# tempctl.net
KiCad netlist of a schematic drawn in EAGLE
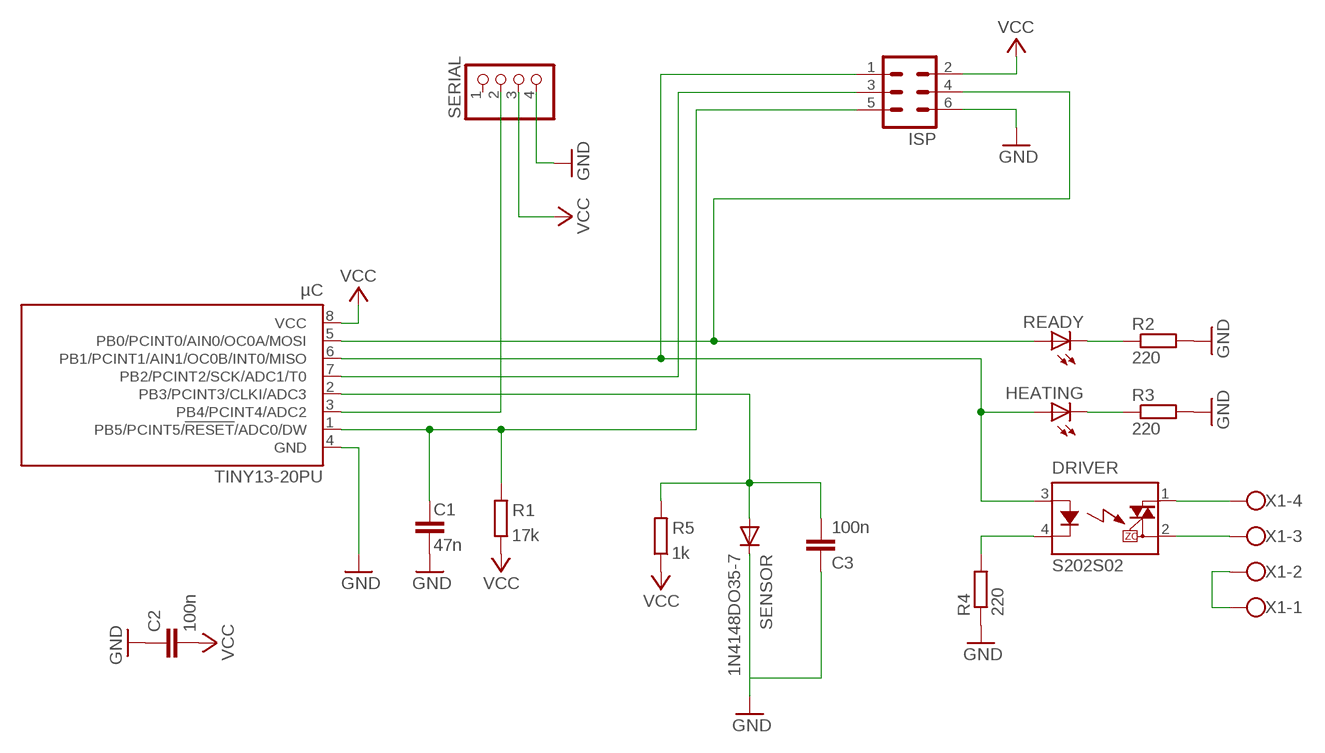
[diagram p0: schematic, sheet 1]

(export (version "E")
  (design (tool "Eeschema 10.0.6"))
  (components
    (comp (ref "C1")
      (value "47n")
      (footprint "eagle-import:C075-032X103")
      (libsource (lib "eagle-import") (part "C-EU075-032X103"))
    )
    (comp (ref "C2")
      (value "100n")
      (footprint "eagle-import:C102-043X133")
      (libsource (lib "eagle-import") (part "C-EU102-043X133"))
    )
    (comp (ref "C3")
      (value "100n")
      (footprint "eagle-import:C102-043X133")
      (libsource (lib "eagle-import") (part "C-EU102-043X133"))
    )
    (comp (ref "DRIVER")
      (value "S202S02")
      (footprint "eagle-import:S202S02")
      (fields (field (name "MPN") "S202S02F"))
      (libsource (lib "eagle-import") (part "S02S022"))
    )
    (comp (ref "HEATING")
      (value "LED3MM")
      (footprint "eagle-import:LED3MM")
      (libsource (lib "eagle-import") (part "LED3MM"))
    )
    (comp (ref "ISP")
      (value "ML6")
      (footprint "eagle-import:ML6")
      (libsource (lib "eagle-import") (part "ML6"))
    )
    (comp (ref "R1")
      (value "17k")
      (footprint "eagle-import:0207_10")
      (libsource (lib "eagle-import") (part "R-EU_0207/10"))
    )
    (comp (ref "R2")
      (value "220")
      (footprint "eagle-import:0309_12")
      (libsource (lib "eagle-import") (part "R-EU_0309/12"))
    )
    (comp (ref "R3")
      (value "220")
      (footprint "eagle-import:0309_12")
      (libsource (lib "eagle-import") (part "R-EU_0309/12"))
    )
    (comp (ref "R4")
      (value "220")
      (footprint "eagle-import:0309_12")
      (libsource (lib "eagle-import") (part "R-EU_0309/12"))
    )
    (comp (ref "R5")
      (value "1k")
      (footprint "eagle-import:0207_10")
      (libsource (lib "eagle-import") (part "R-EU_0207/10"))
    )
    (comp (ref "READY")
      (value "LED3MM")
      (footprint "eagle-import:LED3MM")
      (libsource (lib "eagle-import") (part "LED3MM"))
    )
    (comp (ref "SENSOR")
      (value "1N4148DO35-7")
      (footprint "eagle-import:DO35-7")
      (libsource (lib "eagle-import") (part "1N4148DO35-7"))
    )
    (comp (ref "SERIAL")
      (value "PINHD-1X4")
      (footprint "eagle-import:1X04")
      (libsource (lib "eagle-import") (part "PINHD-1X4"))
    )
    (comp (ref "X1")
      (value "W237-4")
      (footprint "eagle-import:W237-4")
      (libsource (lib "eagle-import") (part "W237-4"))
    )
    (comp (ref "µC")
      (value "TINY13-20PU")
      (footprint "eagle-import:DIL08")
      (fields (field (name "MPN") "ATTINY13-20PU"))
      (libsource (lib "eagle-import") (part "TINY13PU-20"))
    )
  )
  (nets
    (net (code "1") (name "GND") (class "Default")
      (node (ref "C1") (pin "2") (pinfunction "2_2") (pintype "passive"))
      (node (ref "C2") (pin "1") (pinfunction "1_1") (pintype "passive"))
      (node (ref "C3") (pin "1") (pinfunction "1_1") (pintype "passive"))
      (node (ref "ISP") (pin "6") (pinfunction "6_6") (pintype "passive"))
      (node (ref "R2") (pin "2") (pinfunction "2_2") (pintype "passive"))
      (node (ref "R3") (pin "2") (pinfunction "2_2") (pintype "passive"))
      (node (ref "R4") (pin "1") (pinfunction "1_1") (pintype "passive"))
      (node (ref "SENSOR") (pin "C") (pinfunction "C_C") (pintype "passive"))
      (node (ref "SERIAL") (pin "4") (pinfunction "4_4") (pintype "passive"))
      (node (ref "µC") (pin "4") (pinfunction "GND_4") (pintype "power_in"))
    )
    (net (code "2") (name "Net-(DRIVER-A)") (class "Default")
      (node (ref "DRIVER") (pin "3") (pinfunction "A_3") (pintype "passive"))
      (node (ref "HEATING") (pin "A") (pinfunction "A_A") (pintype "passive"))
      (node (ref "ISP") (pin "1") (pinfunction "1_1") (pintype "passive"))
      (node (ref "µC") (pin "6") (pinfunction "PB1/PCINT1/AIN1/OC0B/INT0/MISO_6") (pintype "bidirectional"))
    )
    (net (code "3") (name "Net-(DRIVER-DS1)") (class "Default")
      (node (ref "DRIVER") (pin "1") (pinfunction "DS1_1") (pintype "passive"))
      (node (ref "X1") (pin "4") (pinfunction "KL_4") (pintype "passive"))
    )
    (net (code "4") (name "Net-(DRIVER-DS2)") (class "Default")
      (node (ref "DRIVER") (pin "2") (pinfunction "DS2_2") (pintype "passive"))
      (node (ref "X1") (pin "3") (pinfunction "KL_3") (pintype "passive"))
    )
    (net (code "5") (name "Net-(DRIVER-K)") (class "Default")
      (node (ref "DRIVER") (pin "4") (pinfunction "K_4") (pintype "passive"))
      (node (ref "R4") (pin "2") (pinfunction "2_2") (pintype "passive"))
    )
    (net (code "6") (name "Net-(HEATING-C)") (class "Default")
      (node (ref "HEATING") (pin "K") (pinfunction "C_K") (pintype "passive"))
      (node (ref "R3") (pin "1") (pinfunction "1_1") (pintype "passive"))
    )
    (net (code "7") (name "Net-(READY-C)") (class "Default")
      (node (ref "R2") (pin "1") (pinfunction "1_1") (pintype "passive"))
      (node (ref "READY") (pin "K") (pinfunction "C_K") (pintype "passive"))
    )
    (net (code "8") (name "Net-(X1A-KL)") (class "Default")
      (node (ref "X1") (pin "1") (pinfunction "KL_1") (pintype "passive"))
      (node (ref "X1") (pin "2") (pinfunction "KL_2") (pintype "passive"))
    )
    (net (code "9") (name "Net-(µC-PB0{slash}PCINT0{slash}AIN0{slash}OC0A{slash}MOSI)") (class "Default")
      (node (ref "ISP") (pin "4") (pinfunction "4_4") (pintype "passive"))
      (node (ref "READY") (pin "A") (pinfunction "A_A") (pintype "passive"))
      (node (ref "µC") (pin "5") (pinfunction "PB0/PCINT0/AIN0/OC0A/MOSI_5") (pintype "bidirectional"))
    )
    (net (code "10") (name "Net-(µC-PB2{slash}PCINT2{slash}SCK{slash}ADC1{slash}T0)") (class "Default")
      (node (ref "ISP") (pin "3") (pinfunction "3_3") (pintype "passive"))
      (node (ref "µC") (pin "7") (pinfunction "PB2/PCINT2/SCK/ADC1/T0_7") (pintype "bidirectional"))
    )
    (net (code "11") (name "Net-(µC-PB3{slash}PCINT3{slash}CLKI{slash}ADC3)") (class "Default")
      (node (ref "C3") (pin "2") (pinfunction "2_2") (pintype "passive"))
      (node (ref "R5") (pin "2") (pinfunction "2_2") (pintype "passive"))
      (node (ref "SENSOR") (pin "A") (pinfunction "A_A") (pintype "passive"))
      (node (ref "µC") (pin "2") (pinfunction "PB3/PCINT3/CLKI/ADC3_2") (pintype "bidirectional"))
    )
    (net (code "12") (name "Net-(µC-PB4{slash}PCINT4{slash}ADC2)") (class "Default")
      (node (ref "SERIAL") (pin "2") (pinfunction "2_2") (pintype "passive"))
      (node (ref "µC") (pin "3") (pinfunction "PB4/PCINT4/ADC2_3") (pintype "bidirectional"))
    )
    (net (code "13") (name "Net-(µC-PB5{slash}PCINT5{slash}~{RESET}{slash}ADC0{slash}DW)") (class "Default")
      (node (ref "C1") (pin "1") (pinfunction "1_1") (pintype "passive"))
      (node (ref "ISP") (pin "5") (pinfunction "5_5") (pintype "passive"))
      (node (ref "R1") (pin "2") (pinfunction "2_2") (pintype "passive"))
      (node (ref "µC") (pin "1") (pinfunction "PB5/PCINT5/~{RESET}/ADC0/DW_1") (pintype "bidirectional"))
    )
    (net (code "14") (name "VCC") (class "Default")
      (node (ref "C2") (pin "2") (pinfunction "2_2") (pintype "passive"))
      (node (ref "ISP") (pin "2") (pinfunction "2_2") (pintype "passive"))
      (node (ref "R1") (pin "1") (pinfunction "1_1") (pintype "passive"))
      (node (ref "R5") (pin "1") (pinfunction "1_1") (pintype "passive"))
      (node (ref "SERIAL") (pin "3") (pinfunction "3_3") (pintype "passive"))
      (node (ref "µC") (pin "8") (pinfunction "VCC_8") (pintype "power_in"))
    )
    (net (code "15") (name "unconnected-(SERIAL-Pad1)") (class "Default")
      (node (ref "SERIAL") (pin "1") (pinfunction "1_1") (pintype "passive"))
    )
  )
)
